# CPCIS_Connectors_P1_P6.net
KiCad netlist of a schematic drawn in Altium Designer
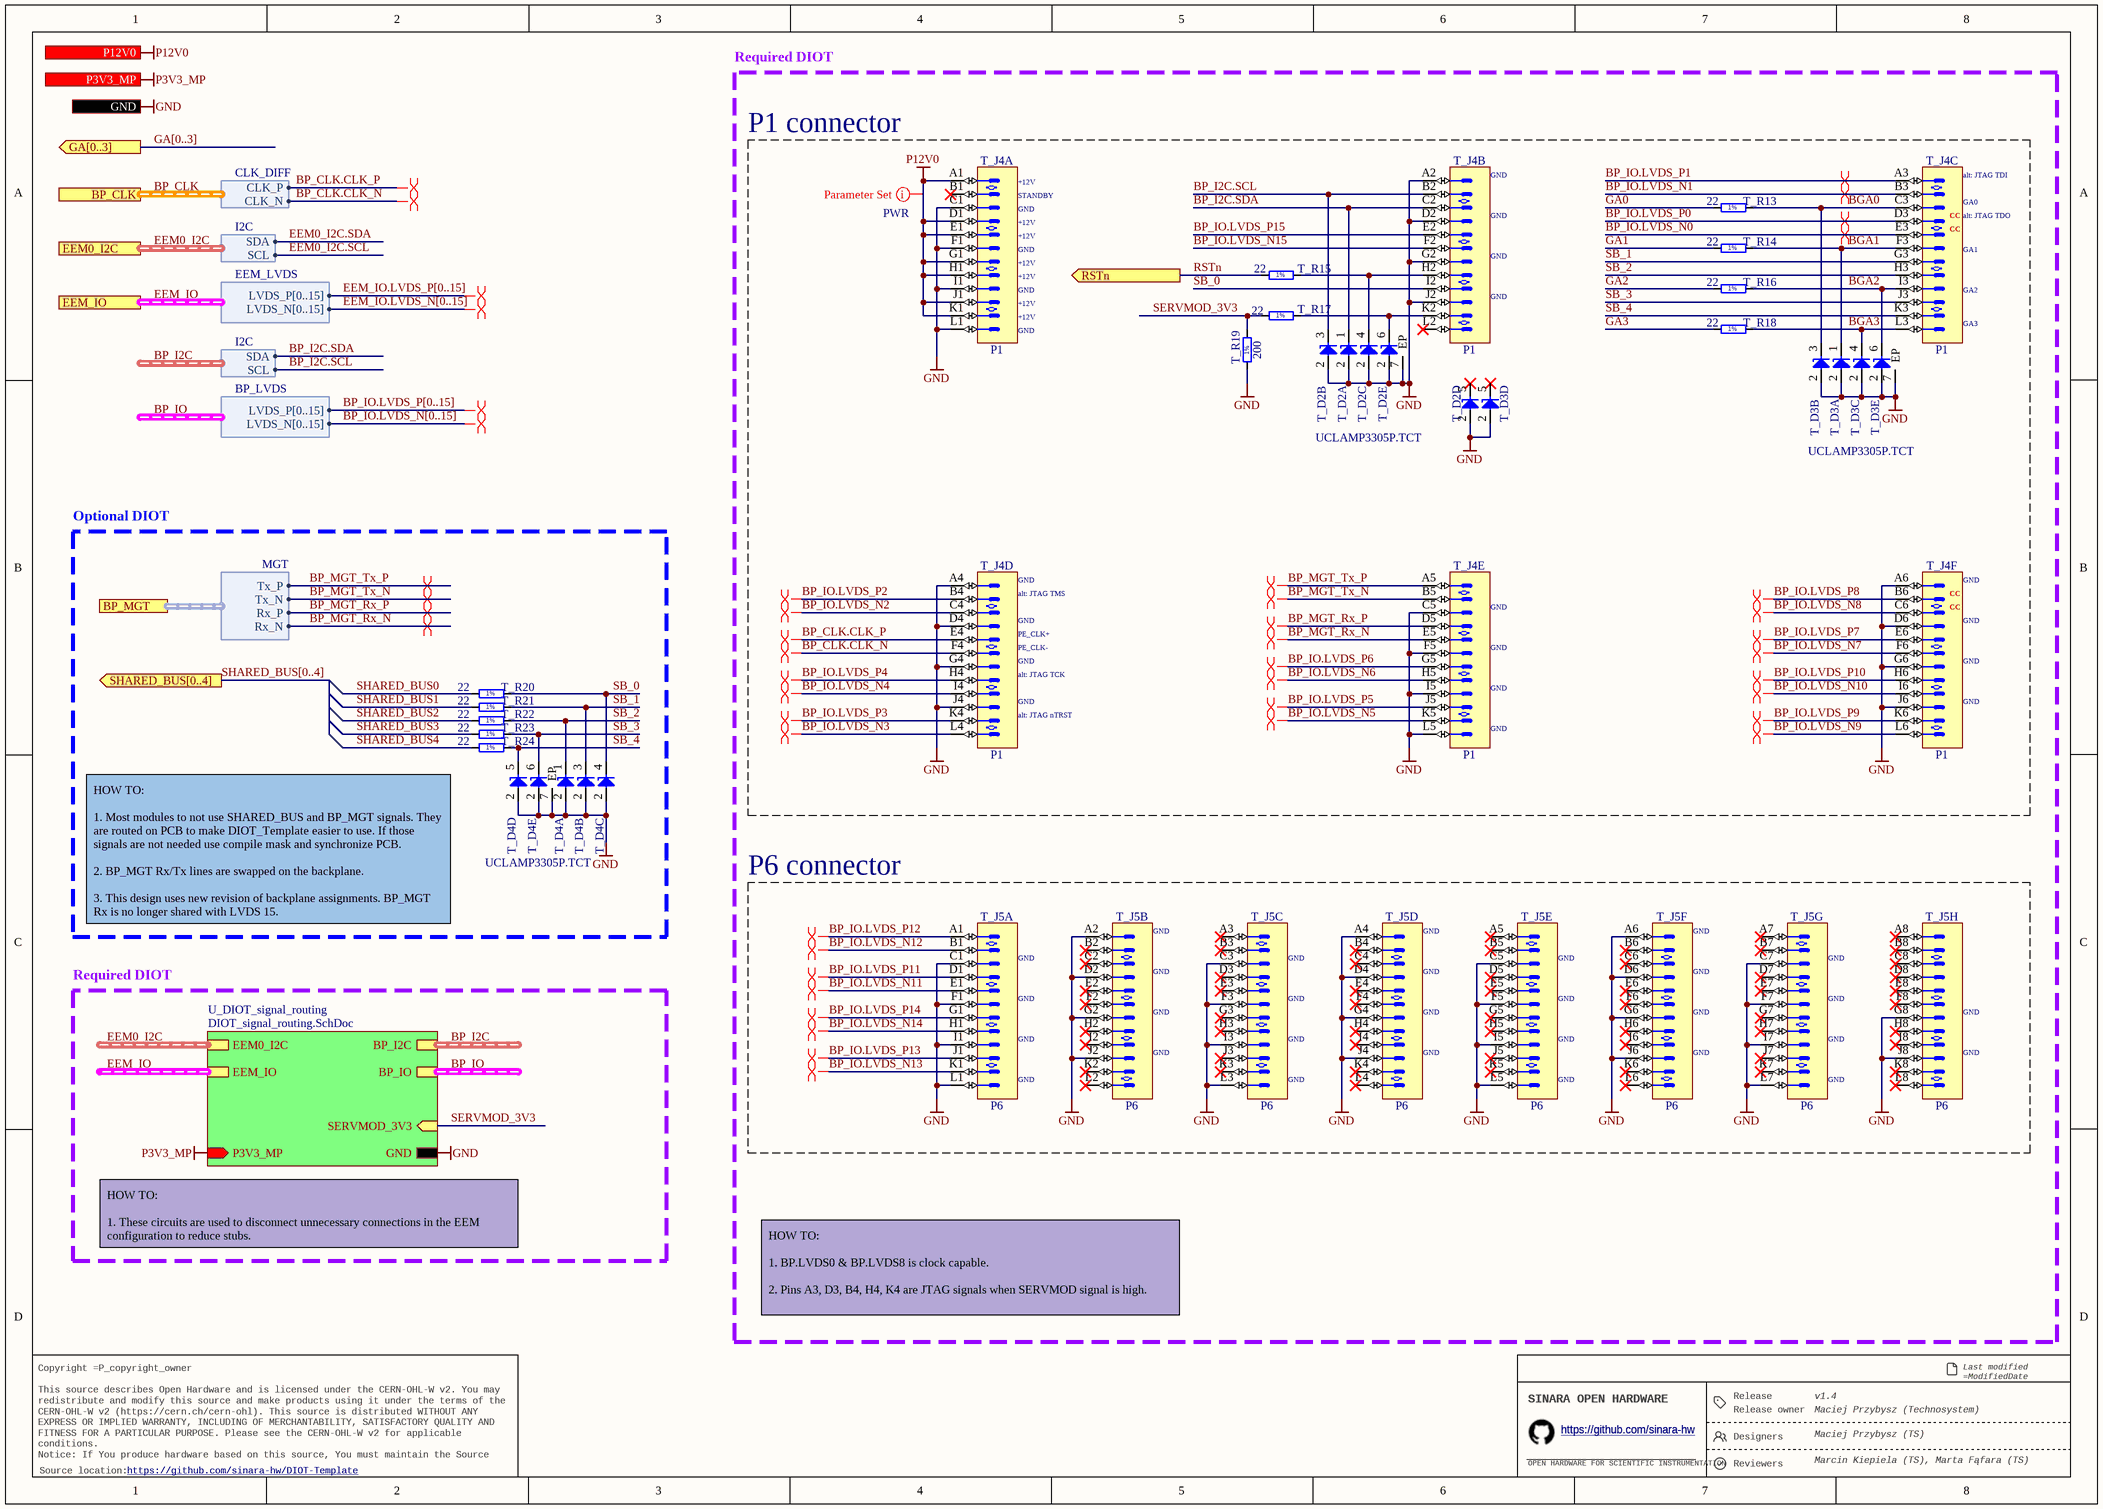
[diagram p0: CPCIS_Connectors_P1_P6.SchDoc]

(export (version "E")
  (design (tool "Eeschema 10.0.6"))
  (components
    (comp (ref "T_D2")
      (value "UCLAMP3305P.TCT")
      (footprint "SON50P160X65_HS-7N")
      (description "Diode TVS Quint Common Anode Uni-Dir 3.3V 40W 6-Pin SLP EP T/R")
      (libsource (lib "TechnoSystem Workspace") (part "D-AK-2"))
    )
    (comp (ref "T_D3")
      (value "UCLAMP3305P.TCT")
      (footprint "SON50P160X65_HS-7N")
      (description "Diode TVS Quint Common Anode Uni-Dir 3.3V 40W 6-Pin SLP EP T/R")
      (libsource (lib "TechnoSystem Workspace") (part "D-AK-2"))
    )
    (comp (ref "T_D4")
      (value "UCLAMP3305P.TCT")
      (footprint "SON50P160X65_HS-7N")
      (description "Diode TVS Quint Common Anode Uni-Dir 3.3V 40W 6-Pin SLP EP T/R")
      (libsource (lib "TechnoSystem Workspace") (part "D-AK-2"))
    )
    (comp (ref "T_J4")
      (value "P1")
      (footprint "AMPHENOL_10052825-101LF")
      (description "72 Contacts Header, 6 Columns, 4 Pairs per Column")
      (fields
        (field (name "PART NUMBER") "AMPHENOL_10052825-101LF")
        (field (name "MANUFACTURER") "AMPHENOL")
        (field (name "AUTHOR") "CERN DEM MR")
      )
      (libsource (lib "Connectors") (part "AMPHENOL_10052825-101LF"))
    )
    (comp (ref "T_J5")
      (value "P6")
      (footprint "AMPHENOL_10052838-101LF")
      (description "96 Contacts Header, 8 Columns, 4 Pairs per Column")
      (fields
        (field (name "PART NUMBER") "AMPHENOL_10052838-101LF")
        (field (name "MANUFACTURER") "AMPHENOL")
        (field (name "AUTHOR") "CERN DEM MR")
      )
      (libsource (lib "Connectors") (part "AMPHENOL_10052838-101LF"))
    )
    (comp (ref "T_R13")
      (value "22")
      (footprint "RESC1005X40N")
      (description "Resistor - 1%")
      (fields
        (field (name "PART NUMBER") "R0402_22R_1%_0.0625W_100PPM")
        (field (name "POWER") "0.0625W")
        (field (name "AUTHOR") "CERN DEM JLC")
      )
      (libsource (lib "Resistors") (part "Resistor - 1%"))
    )
    (comp (ref "T_R14")
      (value "22")
      (footprint "RESC1005X40N")
      (description "Resistor - 1%")
      (fields
        (field (name "PART NUMBER") "R0402_22R_1%_0.0625W_100PPM")
        (field (name "POWER") "0.0625W")
        (field (name "AUTHOR") "CERN DEM JLC")
      )
      (libsource (lib "Resistors") (part "Resistor - 1%"))
    )
    (comp (ref "T_R15")
      (value "22")
      (footprint "RESC1005X40N")
      (description "Resistor - 1%")
      (fields
        (field (name "PART NUMBER") "R0402_22R_1%_0.0625W_100PPM")
        (field (name "POWER") "0.0625W")
        (field (name "AUTHOR") "CERN DEM JLC")
      )
      (libsource (lib "Resistors") (part "Resistor - 1%"))
    )
    (comp (ref "T_R16")
      (value "22")
      (footprint "RESC1005X40N")
      (description "Resistor - 1%")
      (fields
        (field (name "PART NUMBER") "R0402_22R_1%_0.0625W_100PPM")
        (field (name "POWER") "0.0625W")
        (field (name "AUTHOR") "CERN DEM JLC")
      )
      (libsource (lib "Resistors") (part "Resistor - 1%"))
    )
    (comp (ref "T_R17")
      (value "22")
      (footprint "RESC1005X40N")
      (description "Resistor - 1%")
      (fields
        (field (name "PART NUMBER") "R0402_22R_1%_0.0625W_100PPM")
        (field (name "POWER") "0.0625W")
        (field (name "AUTHOR") "CERN DEM JLC")
      )
      (libsource (lib "Resistors") (part "Resistor - 1%"))
    )
    (comp (ref "T_R18")
      (value "22")
      (footprint "RESC1005X40N")
      (description "Resistor - 1%")
      (fields
        (field (name "PART NUMBER") "R0402_22R_1%_0.0625W_100PPM")
        (field (name "POWER") "0.0625W")
        (field (name "AUTHOR") "CERN DEM JLC")
      )
      (libsource (lib "Resistors") (part "Resistor - 1%"))
    )
    (comp (ref "T_R19")
      (value "200")
      (footprint "RESC1005X40N")
      (description "Resistor - 1%")
      (fields
        (field (name "PART NUMBER") "R0402_200R_1%_0.0625W_100PPM")
        (field (name "POWER") "0.0625W")
        (field (name "AUTHOR") "CERN DEM JLC")
      )
      (libsource (lib "Resistors") (part "Resistor - 1%"))
    )
    (comp (ref "T_R20")
      (value "22")
      (footprint "RESC1005X40N")
      (description "Resistor - 1%")
      (fields
        (field (name "PART NUMBER") "R0402_22R_1%_0.0625W_100PPM")
        (field (name "POWER") "0.0625W")
        (field (name "AUTHOR") "CERN DEM JLC")
      )
      (libsource (lib "Resistors") (part "Resistor - 1%"))
    )
    (comp (ref "T_R21")
      (value "22")
      (footprint "RESC1005X40N")
      (description "Resistor - 1%")
      (fields
        (field (name "PART NUMBER") "R0402_22R_1%_0.0625W_100PPM")
        (field (name "POWER") "0.0625W")
        (field (name "AUTHOR") "CERN DEM JLC")
      )
      (libsource (lib "Resistors") (part "Resistor - 1%"))
    )
    (comp (ref "T_R22")
      (value "22")
      (footprint "RESC1005X40N")
      (description "Resistor - 1%")
      (fields
        (field (name "PART NUMBER") "R0402_22R_1%_0.0625W_100PPM")
        (field (name "POWER") "0.0625W")
        (field (name "AUTHOR") "CERN DEM JLC")
      )
      (libsource (lib "Resistors") (part "Resistor - 1%"))
    )
    (comp (ref "T_R23")
      (value "22")
      (footprint "RESC1005X40N")
      (description "Resistor - 1%")
      (fields
        (field (name "PART NUMBER") "R0402_22R_1%_0.0625W_100PPM")
        (field (name "POWER") "0.0625W")
        (field (name "AUTHOR") "CERN DEM JLC")
      )
      (libsource (lib "Resistors") (part "Resistor - 1%"))
    )
    (comp (ref "T_R24")
      (value "22")
      (footprint "RESC1005X40N")
      (description "Resistor - 1%")
      (fields
        (field (name "PART NUMBER") "R0402_22R_1%_0.0625W_100PPM")
        (field (name "POWER") "0.0625W")
        (field (name "AUTHOR") "CERN DEM JLC")
      )
      (libsource (lib "Resistors") (part "Resistor - 1%"))
    )
  )
  (nets
    (net (code "43") (name "/BGA0") (class "Default")
      (node (ref "T_D3") (pin "3") (pinfunction "C_3") (pintype "passive"))
      (node (ref "T_J4") (pin "C3") (pinfunction "C3_C3") (pintype "bidirectional"))
      (node (ref "T_R13") (pin "2") (pinfunction "2_2") (pintype "passive"))
    )
    (net (code "44") (name "/BGA1") (class "Default")
      (node (ref "T_D3") (pin "1") (pinfunction "C_1") (pintype "passive"))
      (node (ref "T_J4") (pin "F3") (pinfunction "F3_F3") (pintype "bidirectional"))
      (node (ref "T_R14") (pin "2") (pinfunction "2_2") (pintype "passive"))
    )
    (net (code "45") (name "/BGA2") (class "Default")
      (node (ref "T_D3") (pin "6") (pinfunction "C_6") (pintype "passive"))
      (node (ref "T_J4") (pin "I3") (pinfunction "I3_I3") (pintype "bidirectional"))
      (node (ref "T_R16") (pin "2") (pinfunction "2_2") (pintype "passive"))
    )
    (net (code "46") (name "/BGA3") (class "Default")
      (node (ref "T_D3") (pin "4") (pinfunction "C_4") (pintype "passive"))
      (node (ref "T_J4") (pin "L3") (pinfunction "L3_L3") (pintype "bidirectional"))
      (node (ref "T_R18") (pin "2") (pinfunction "2_2") (pintype "passive"))
    )
    (net (code "47") (name "/BP_CLK.CLK_N") (class "Default")
      (node (ref "T_J4") (pin "F4") (pinfunction "F4_F4") (pintype "bidirectional"))
    )
    (net (code "48") (name "/BP_CLK.CLK_P") (class "Default")
      (node (ref "T_J4") (pin "E4") (pinfunction "E4_E4") (pintype "bidirectional"))
    )
    (net (code "50") (name "/BP_I2C.SCL") (class "Default")
      (node (ref "T_D2") (pin "3") (pinfunction "C_3") (pintype "passive"))
      (node (ref "T_J4") (pin "B2") (pinfunction "B2_B2") (pintype "bidirectional"))
    )
    (net (code "51") (name "/BP_I2C.SDA") (class "Default")
      (node (ref "T_D2") (pin "1") (pinfunction "C_1") (pintype "passive"))
      (node (ref "T_J4") (pin "C2") (pinfunction "C2_C2") (pintype "bidirectional"))
    )
    (net (code "53") (name "/BP_IO.LVDS_N0") (class "Default")
      (node (ref "T_J4") (pin "E3") (pinfunction "E3_E3") (pintype "bidirectional"))
    )
    (net (code "54") (name "/BP_IO.LVDS_N1") (class "Default")
      (node (ref "T_J4") (pin "B3") (pinfunction "B3_B3") (pintype "bidirectional"))
    )
    (net (code "55") (name "/BP_IO.LVDS_N2") (class "Default")
      (node (ref "T_J4") (pin "C4") (pinfunction "C4_C4") (pintype "bidirectional"))
    )
    (net (code "56") (name "/BP_IO.LVDS_N3") (class "Default")
      (node (ref "T_J4") (pin "L4") (pinfunction "L4_L4") (pintype "bidirectional"))
    )
    (net (code "57") (name "/BP_IO.LVDS_N4") (class "Default")
      (node (ref "T_J4") (pin "I4") (pinfunction "I4_I4") (pintype "bidirectional"))
    )
    (net (code "58") (name "/BP_IO.LVDS_N5") (class "Default")
      (node (ref "T_J4") (pin "K5") (pinfunction "K5_K5") (pintype "bidirectional"))
    )
    (net (code "59") (name "/BP_IO.LVDS_N6") (class "Default")
      (node (ref "T_J4") (pin "H5") (pinfunction "H5_H5") (pintype "bidirectional"))
    )
    (net (code "60") (name "/BP_IO.LVDS_N7") (class "Default")
      (node (ref "T_J4") (pin "F6") (pinfunction "F6_F6") (pintype "bidirectional"))
    )
    (net (code "61") (name "/BP_IO.LVDS_N8") (class "Default")
      (node (ref "T_J4") (pin "C6") (pinfunction "C6_C6") (pintype "bidirectional"))
    )
    (net (code "62") (name "/BP_IO.LVDS_N9") (class "Default")
      (node (ref "T_J4") (pin "L6") (pinfunction "L6_L6") (pintype "bidirectional"))
    )
    (net (code "63") (name "/BP_IO.LVDS_N10") (class "Default")
      (node (ref "T_J4") (pin "I6") (pinfunction "I6_I6") (pintype "bidirectional"))
    )
    (net (code "64") (name "/BP_IO.LVDS_N11") (class "Default")
      (node (ref "T_J5") (pin "E1") (pinfunction "E1_E1") (pintype "bidirectional"))
    )
    (net (code "65") (name "/BP_IO.LVDS_N12") (class "Default")
      (node (ref "T_J5") (pin "B1") (pinfunction "B1_B1") (pintype "bidirectional"))
    )
    (net (code "66") (name "/BP_IO.LVDS_N13") (class "Default")
      (node (ref "T_J5") (pin "K1") (pinfunction "K1_K1") (pintype "bidirectional"))
    )
    (net (code "67") (name "/BP_IO.LVDS_N14") (class "Default")
      (node (ref "T_J5") (pin "H1") (pinfunction "H1_H1") (pintype "bidirectional"))
    )
    (net (code "68") (name "/BP_IO.LVDS_N15") (class "Default")
      (node (ref "T_J4") (pin "F2") (pinfunction "F2_F2") (pintype "bidirectional"))
    )
    (net (code "70") (name "/BP_IO.LVDS_P0") (class "Default")
      (node (ref "T_J4") (pin "D3") (pinfunction "D3_D3") (pintype "bidirectional"))
    )
    (net (code "71") (name "/BP_IO.LVDS_P1") (class "Default")
      (node (ref "T_J4") (pin "A3") (pinfunction "A3_A3") (pintype "bidirectional"))
    )
    (net (code "72") (name "/BP_IO.LVDS_P2") (class "Default")
      (node (ref "T_J4") (pin "B4") (pinfunction "B4_B4") (pintype "bidirectional"))
    )
    (net (code "73") (name "/BP_IO.LVDS_P3") (class "Default")
      (node (ref "T_J4") (pin "K4") (pinfunction "K4_K4") (pintype "bidirectional"))
    )
    (net (code "74") (name "/BP_IO.LVDS_P4") (class "Default")
      (node (ref "T_J4") (pin "H4") (pinfunction "H4_H4") (pintype "bidirectional"))
    )
    (net (code "75") (name "/BP_IO.LVDS_P5") (class "Default")
      (node (ref "T_J4") (pin "J5") (pinfunction "J5_J5") (pintype "bidirectional"))
    )
    (net (code "76") (name "/BP_IO.LVDS_P6") (class "Default")
      (node (ref "T_J4") (pin "G5") (pinfunction "G5_G5") (pintype "bidirectional"))
    )
    (net (code "77") (name "/BP_IO.LVDS_P7") (class "Default")
      (node (ref "T_J4") (pin "E6") (pinfunction "E6_E6") (pintype "bidirectional"))
    )
    (net (code "78") (name "/BP_IO.LVDS_P8") (class "Default")
      (node (ref "T_J4") (pin "B6") (pinfunction "B6_B6") (pintype "bidirectional"))
    )
    (net (code "79") (name "/BP_IO.LVDS_P9") (class "Default")
      (node (ref "T_J4") (pin "K6") (pinfunction "K6_K6") (pintype "bidirectional"))
    )
    (net (code "80") (name "/BP_IO.LVDS_P10") (class "Default")
      (node (ref "T_J4") (pin "H6") (pinfunction "H6_H6") (pintype "bidirectional"))
    )
    (net (code "81") (name "/BP_IO.LVDS_P11") (class "Default")
      (node (ref "T_J5") (pin "D1") (pinfunction "D1_D1") (pintype "bidirectional"))
    )
    (net (code "82") (name "/BP_IO.LVDS_P12") (class "Default")
      (node (ref "T_J5") (pin "A1") (pinfunction "A1_A1") (pintype "bidirectional"))
    )
    (net (code "83") (name "/BP_IO.LVDS_P13") (class "Default")
      (node (ref "T_J5") (pin "J1") (pinfunction "J1_J1") (pintype "bidirectional"))
    )
    (net (code "84") (name "/BP_IO.LVDS_P14") (class "Default")
      (node (ref "T_J5") (pin "G1") (pinfunction "G1_G1") (pintype "bidirectional"))
    )
    (net (code "85") (name "/BP_IO.LVDS_P15") (class "Default")
      (node (ref "T_J4") (pin "E2") (pinfunction "E2_E2") (pintype "bidirectional"))
    )
    (net (code "88") (name "/BP_MGT_Rx_N") (class "Default")
      (node (ref "T_J4") (pin "E5") (pinfunction "E5_E5") (pintype "bidirectional"))
    )
    (net (code "89") (name "/BP_MGT_Rx_P") (class "Default")
      (node (ref "T_J4") (pin "D5") (pinfunction "D5_D5") (pintype "bidirectional"))
    )
    (net (code "90") (name "/BP_MGT_Tx_N") (class "Default")
      (node (ref "T_J4") (pin "B5") (pinfunction "B5_B5") (pintype "bidirectional"))
    )
    (net (code "91") (name "/BP_MGT_Tx_P") (class "Default")
      (node (ref "T_J4") (pin "A5") (pinfunction "A5_A5") (pintype "bidirectional"))
    )
    (net (code "98") (name "/GA0") (class "Default")
      (node (ref "T_R13") (pin "1") (pinfunction "1_1") (pintype "passive"))
    )
    (net (code "99") (name "/GA1") (class "Default")
      (node (ref "T_R14") (pin "1") (pinfunction "1_1") (pintype "passive"))
    )
    (net (code "100") (name "/GA2") (class "Default")
      (node (ref "T_R16") (pin "1") (pinfunction "1_1") (pintype "passive"))
    )
    (net (code "101") (name "/GA3") (class "Default")
      (node (ref "T_R18") (pin "1") (pinfunction "1_1") (pintype "passive"))
    )
    (net (code "103") (name "/RSTn") (class "Default")
      (node (ref "T_R15") (pin "1") (pinfunction "1_1") (pintype "passive"))
    )
    (net (code "104") (name "/SB_0") (class "Default")
      (node (ref "T_D4") (pin "4") (pinfunction "C_4") (pintype "passive"))
      (node (ref "T_J4") (pin "I2") (pinfunction "I2_I2") (pintype "bidirectional"))
      (node (ref "T_R20") (pin "2") (pinfunction "2_2") (pintype "passive"))
    )
    (net (code "105") (name "/SB_1") (class "Default")
      (node (ref "T_D4") (pin "3") (pinfunction "C_3") (pintype "passive"))
      (node (ref "T_J4") (pin "G3") (pinfunction "G3_G3") (pintype "bidirectional"))
      (node (ref "T_R21") (pin "2") (pinfunction "2_2") (pintype "passive"))
    )
    (net (code "106") (name "/SB_2") (class "Default")
      (node (ref "T_D4") (pin "1") (pinfunction "C_1") (pintype "passive"))
      (node (ref "T_J4") (pin "H3") (pinfunction "H3_H3") (pintype "bidirectional"))
      (node (ref "T_R22") (pin "2") (pinfunction "2_2") (pintype "passive"))
    )
    (net (code "107") (name "/SB_3") (class "Default")
      (node (ref "T_D4") (pin "6") (pinfunction "C_6") (pintype "passive"))
      (node (ref "T_J4") (pin "J3") (pinfunction "J3_J3") (pintype "bidirectional"))
      (node (ref "T_R23") (pin "2") (pinfunction "2_2") (pintype "passive"))
    )
    (net (code "108") (name "/SB_4") (class "Default")
      (node (ref "T_D4") (pin "5") (pinfunction "C_5") (pintype "passive"))
      (node (ref "T_J4") (pin "K3") (pinfunction "K3_K3") (pintype "bidirectional"))
      (node (ref "T_R24") (pin "2") (pinfunction "2_2") (pintype "passive"))
    )
    (net (code "109") (name "/SERVMOD_3V3") (class "Default")
      (node (ref "T_R17") (pin "1") (pinfunction "1_1") (pintype "passive"))
      (node (ref "T_R19") (pin "2") (pinfunction "2_2") (pintype "passive"))
    )
    (net (code "110") (name "/SHARED_BUS0") (class "Default")
      (node (ref "T_R20") (pin "1") (pinfunction "1_1") (pintype "passive"))
    )
    (net (code "111") (name "/SHARED_BUS1") (class "Default")
      (node (ref "T_R21") (pin "1") (pinfunction "1_1") (pintype "passive"))
    )
    (net (code "112") (name "/SHARED_BUS2") (class "Default")
      (node (ref "T_R22") (pin "1") (pinfunction "1_1") (pintype "passive"))
    )
    (net (code "113") (name "/SHARED_BUS3") (class "Default")
      (node (ref "T_R23") (pin "1") (pinfunction "1_1") (pintype "passive"))
    )
    (net (code "114") (name "/SHARED_BUS4") (class "Default")
      (node (ref "T_R24") (pin "1") (pinfunction "1_1") (pintype "passive"))
    )
    (net (code "121") (name "GND") (class "Default")
      (node (ref "T_D2") (pin "2") (pinfunction "A_2") (pintype "passive"))
      (node (ref "T_D2") (pin "7") (pinfunction "EP_7") (pintype "passive"))
      (node (ref "T_D3") (pin "2") (pinfunction "A_2") (pintype "passive"))
      (node (ref "T_D3") (pin "7") (pinfunction "EP_7") (pintype "passive"))
      (node (ref "T_D4") (pin "2") (pinfunction "A_2") (pintype "passive"))
      (node (ref "T_D4") (pin "7") (pinfunction "EP_7") (pintype "passive"))
      (node (ref "T_J4") (pin "A2") (pinfunction "A2_A2") (pintype "bidirectional"))
      (node (ref "T_J4") (pin "A4") (pinfunction "A4_A4") (pintype "bidirectional"))
      (node (ref "T_J4") (pin "A6") (pinfunction "A6_A6") (pintype "bidirectional"))
      (node (ref "T_J4") (pin "C1") (pinfunction "C1_C1") (pintype "bidirectional"))
      (node (ref "T_J4") (pin "C5") (pinfunction "C5_C5") (pintype "bidirectional"))
      (node (ref "T_J4") (pin "D2") (pinfunction "D2_D2") (pintype "bidirectional"))
      (node (ref "T_J4") (pin "D4") (pinfunction "D4_D4") (pintype "bidirectional"))
      (node (ref "T_J4") (pin "D6") (pinfunction "D6_D6") (pintype "bidirectional"))
      (node (ref "T_J4") (pin "F1") (pinfunction "F1_F1") (pintype "bidirectional"))
      (node (ref "T_J4") (pin "F5") (pinfunction "F5_F5") (pintype "bidirectional"))
      (node (ref "T_J4") (pin "G2") (pinfunction "G2_G2") (pintype "bidirectional"))
      (node (ref "T_J4") (pin "G4") (pinfunction "G4_G4") (pintype "bidirectional"))
      (node (ref "T_J4") (pin "G6") (pinfunction "G6_G6") (pintype "bidirectional"))
      (node (ref "T_J4") (pin "I1") (pinfunction "I1_I1") (pintype "bidirectional"))
      (node (ref "T_J4") (pin "I5") (pinfunction "I5_I5") (pintype "bidirectional"))
      (node (ref "T_J4") (pin "J2") (pinfunction "J2_J2") (pintype "bidirectional"))
      (node (ref "T_J4") (pin "J4") (pinfunction "J4_J4") (pintype "bidirectional"))
      (node (ref "T_J4") (pin "J6") (pinfunction "J6_J6") (pintype "bidirectional"))
      (node (ref "T_J4") (pin "L1") (pinfunction "L1_L1") (pintype "bidirectional"))
      (node (ref "T_J4") (pin "L5") (pinfunction "L5_L5") (pintype "bidirectional"))
      (node (ref "T_J5") (pin "A2") (pinfunction "A2_A2") (pintype "bidirectional"))
      (node (ref "T_J5") (pin "A4") (pinfunction "A4_A4") (pintype "bidirectional"))
      (node (ref "T_J5") (pin "A6") (pinfunction "A6_A6") (pintype "bidirectional"))
      (node (ref "T_J5") (pin "C1") (pinfunction "C1_C1") (pintype "bidirectional"))
      (node (ref "T_J5") (pin "C3") (pinfunction "C3_C3") (pintype "bidirectional"))
      (node (ref "T_J5") (pin "C5") (pinfunction "C5_C5") (pintype "bidirectional"))
      (node (ref "T_J5") (pin "C7") (pinfunction "C7_C7") (pintype "bidirectional"))
      (node (ref "T_J5") (pin "D2") (pinfunction "D2_D2") (pintype "bidirectional"))
      (node (ref "T_J5") (pin "D4") (pinfunction "D4_D4") (pintype "bidirectional"))
      (node (ref "T_J5") (pin "D6") (pinfunction "D6_D6") (pintype "bidirectional"))
      (node (ref "T_J5") (pin "F1") (pinfunction "F1_F1") (pintype "bidirectional"))
      (node (ref "T_J5") (pin "F3") (pinfunction "F3_F3") (pintype "bidirectional"))
      (node (ref "T_J5") (pin "F5") (pinfunction "F5_F5") (pintype "bidirectional"))
      (node (ref "T_J5") (pin "F7") (pinfunction "F7_F7") (pintype "bidirectional"))
      (node (ref "T_J5") (pin "G2") (pinfunction "G2_G2") (pintype "bidirectional"))
      (node (ref "T_J5") (pin "G4") (pinfunction "G4_G4") (pintype "bidirectional"))
      (node (ref "T_J5") (pin "G6") (pinfunction "G6_G6") (pintype "bidirectional"))
      (node (ref "T_J5") (pin "G8") (pinfunction "G8_G8") (pintype "bidirectional"))
      (node (ref "T_J5") (pin "I1") (pinfunction "I1_I1") (pintype "bidirectional"))
      (node (ref "T_J5") (pin "I3") (pinfunction "I3_I3") (pintype "bidirectional"))
      (node (ref "T_J5") (pin "I5") (pinfunction "I5_I5") (pintype "bidirectional"))
      (node (ref "T_J5") (pin "I7") (pinfunction "I7_I7") (pintype "bidirectional"))
      (node (ref "T_J5") (pin "J2") (pinfunction "J2_J2") (pintype "bidirectional"))
      (node (ref "T_J5") (pin "J4") (pinfunction "J4_J4") (pintype "bidirectional"))
      (node (ref "T_J5") (pin "J6") (pinfunction "J6_J6") (pintype "bidirectional"))
      (node (ref "T_J5") (pin "J8") (pinfunction "J8_J8") (pintype "bidirectional"))
      (node (ref "T_J5") (pin "L1") (pinfunction "L1_L1") (pintype "bidirectional"))
      (node (ref "T_J5") (pin "L3") (pinfunction "L3_L3") (pintype "bidirectional"))
      (node (ref "T_J5") (pin "L5") (pinfunction "L5_L5") (pintype "bidirectional"))
      (node (ref "T_J5") (pin "L7") (pinfunction "L7_L7") (pintype "bidirectional"))
      (node (ref "T_R19") (pin "1") (pinfunction "1_1") (pintype "passive"))
    )
    (net (code "122") (name "Net-(T_D2C-C)") (class "Default")
      (node (ref "T_D2") (pin "4") (pinfunction "C_4") (pintype "passive"))
      (node (ref "T_J4") (pin "H2") (pinfunction "H2_H2") (pintype "bidirectional"))
      (node (ref "T_R15") (pin "2") (pinfunction "2_2") (pintype "passive"))
    )
    (net (code "123") (name "Net-(T_D2E-C)") (class "Default")
      (node (ref "T_D2") (pin "6") (pinfunction "C_6") (pintype "passive"))
      (node (ref "T_J4") (pin "K2") (pinfunction "K2_K2") (pintype "bidirectional"))
      (node (ref "T_R17") (pin "2") (pinfunction "2_2") (pintype "passive"))
    )
    (net (code "125") (name "P12V0") (class "Default")
      (node (ref "T_J4") (pin "A1") (pinfunction "A1_A1") (pintype "bidirectional"))
      (node (ref "T_J4") (pin "D1") (pinfunction "D1_D1") (pintype "bidirectional"))
      (node (ref "T_J4") (pin "E1") (pinfunction "E1_E1") (pintype "bidirectional"))
      (node (ref "T_J4") (pin "G1") (pinfunction "G1_G1") (pintype "bidirectional"))
      (node (ref "T_J4") (pin "H1") (pinfunction "H1_H1") (pintype "bidirectional"))
      (node (ref "T_J4") (pin "J1") (pinfunction "J1_J1") (pintype "bidirectional"))
      (node (ref "T_J4") (pin "K1") (pinfunction "K1_K1") (pintype "bidirectional"))
    )
    (net (code "126") (name "unconnected-(T_D2D-C-Pad5)") (class "Default")
      (node (ref "T_D2") (pin "5") (pinfunction "C_5") (pintype "passive+no_connect"))
    )
    (net (code "127") (name "unconnected-(T_D3D-C-Pad5)") (class "Default")
      (node (ref "T_D3") (pin "5") (pinfunction "C_5") (pintype "passive+no_connect"))
    )
    (net (code "128") (name "unconnected-(T_J4-PadB1)") (class "Default")
      (node (ref "T_J4") (pin "B1") (pinfunction "B1_B1") (pintype "bidirectional+no_connect"))
    )
    (net (code "129") (name "unconnected-(T_J4-PadL2)") (class "Default")
      (node (ref "T_J4") (pin "L2") (pinfunction "L2_L2") (pintype "bidirectional+no_connect"))
    )
    (net (code "130") (name "unconnected-(T_J5-PadA3)") (class "Default")
      (node (ref "T_J5") (pin "A3") (pinfunction "A3_A3") (pintype "bidirectional+no_connect"))
    )
    (net (code "131") (name "unconnected-(T_J5-PadA5)") (class "Default")
      (node (ref "T_J5") (pin "A5") (pinfunction "A5_A5") (pintype "bidirectional+no_connect"))
    )
    (net (code "132") (name "unconnected-(T_J5-PadA7)") (class "Default")
      (node (ref "T_J5") (pin "A7") (pinfunction "A7_A7") (pintype "bidirectional+no_connect"))
    )
    (net (code "133") (name "unconnected-(T_J5-PadA8)") (class "Default")
      (node (ref "T_J5") (pin "A8") (pinfunction "A8_A8") (pintype "bidirectional+no_connect"))
    )
    (net (code "134") (name "unconnected-(T_J5-PadB2)") (class "Default")
      (node (ref "T_J5") (pin "B2") (pinfunction "B2_B2") (pintype "bidirectional+no_connect"))
    )
    (net (code "135") (name "unconnected-(T_J5-PadB3)") (class "Default")
      (node (ref "T_J5") (pin "B3") (pinfunction "B3_B3") (pintype "bidirectional+no_connect"))
    )
    (net (code "136") (name "unconnected-(T_J5-PadB4)") (class "Default")
      (node (ref "T_J5") (pin "B4") (pinfunction "B4_B4") (pintype "bidirectional+no_connect"))
    )
    (net (code "137") (name "unconnected-(T_J5-PadB5)") (class "Default")
      (node (ref "T_J5") (pin "B5") (pinfunction "B5_B5") (pintype "bidirectional+no_connect"))
    )
    (net (code "138") (name "unconnected-(T_J5-PadB6)") (class "Default")
      (node (ref "T_J5") (pin "B6") (pinfunction "B6_B6") (pintype "bidirectional+no_connect"))
    )
    (net (code "139") (name "unconnected-(T_J5-PadB7)") (class "Default")
      (node (ref "T_J5") (pin "B7") (pinfunction "B7_B7") (pintype "bidirectional+no_connect"))
    )
    (net (code "140") (name "unconnected-(T_J5-PadB8)") (class "Default")
      (node (ref "T_J5") (pin "B8") (pinfunction "B8_B8") (pintype "bidirectional+no_connect"))
    )
    (net (code "141") (name "unconnected-(T_J5-PadC2)") (class "Default")
      (node (ref "T_J5") (pin "C2") (pinfunction "C2_C2") (pintype "bidirectional+no_connect"))
    )
    (net (code "142") (name "unconnected-(T_J5-PadC4)") (class "Default")
      (node (ref "T_J5") (pin "C4") (pinfunction "C4_C4") (pintype "bidirectional+no_connect"))
    )
    (net (code "143") (name "unconnected-(T_J5-PadC6)") (class "Default")
      (node (ref "T_J5") (pin "C6") (pinfunction "C6_C6") (pintype "bidirectional+no_connect"))
    )
    (net (code "144") (name "unconnected-(T_J5-PadC8)") (class "Default")
      (node (ref "T_J5") (pin "C8") (pinfunction "C8_C8") (pintype "bidirectional+no_connect"))
    )
    (net (code "145") (name "unconnected-(T_J5-PadD3)") (class "Default")
      (node (ref "T_J5") (pin "D3") (pinfunction "D3_D3") (pintype "bidirectional+no_connect"))
    )
    (net (code "146") (name "unconnected-(T_J5-PadD5)") (class "Default")
      (node (ref "T_J5") (pin "D5") (pinfunction "D5_D5") (pintype "bidirectional+no_connect"))
    )
    (net (code "147") (name "unconnected-(T_J5-PadD7)") (class "Default")
      (node (ref "T_J5") (pin "D7") (pinfunction "D7_D7") (pintype "bidirectional+no_connect"))
    )
    (net (code "148") (name "unconnected-(T_J5-PadD8)") (class "Default")
      (node (ref "T_J5") (pin "D8") (pinfunction "D8_D8") (pintype "bidirectional+no_connect"))
    )
    (net (code "149") (name "unconnected-(T_J5-PadE2)") (class "Default")
      (node (ref "T_J5") (pin "E2") (pinfunction "E2_E2") (pintype "bidirectional+no_connect"))
    )
    (net (code "150") (name "unconnected-(T_J5-PadE3)") (class "Default")
      (node (ref "T_J5") (pin "E3") (pinfunction "E3_E3") (pintype "bidirectional+no_connect"))
    )
    (net (code "151") (name "unconnected-(T_J5-PadE4)") (class "Default")
      (node (ref "T_J5") (pin "E4") (pinfunction "E4_E4") (pintype "bidirectional+no_connect"))
    )
    (net (code "152") (name "unconnected-(T_J5-PadE5)") (class "Default")
      (node (ref "T_J5") (pin "E5") (pinfunction "E5_E5") (pintype "bidirectional+no_connect"))
    )
    (net (code "153") (name "unconnected-(T_J5-PadE6)") (class "Default")
      (node (ref "T_J5") (pin "E6") (pinfunction "E6_E6") (pintype "bidirectional+no_connect"))
    )
    (net (code "154") (name "unconnected-(T_J5-PadE7)") (class "Default")
      (node (ref "T_J5") (pin "E7") (pinfunction "E7_E7") (pintype "bidirectional+no_connect"))
    )
    (net (code "155") (name "unconnected-(T_J5-PadE8)") (class "Default")
      (node (ref "T_J5") (pin "E8") (pinfunction "E8_E8") (pintype "bidirectional+no_connect"))
    )
    (net (code "156") (name "unconnected-(T_J5-PadF2)") (class "Default")
      (node (ref "T_J5") (pin "F2") (pinfunction "F2_F2") (pintype "bidirectional+no_connect"))
    )
    (net (code "157") (name "unconnected-(T_J5-PadF4)") (class "Default")
      (node (ref "T_J5") (pin "F4") (pinfunction "F4_F4") (pintype "bidirectional+no_connect"))
    )
    (net (code "158") (name "unconnected-(T_J5-PadF6)") (class "Default")
      (node (ref "T_J5") (pin "F6") (pinfunction "F6_F6") (pintype "bidirectional+no_connect"))
    )
    (net (code "159") (name "unconnected-(T_J5-PadF8)") (class "Default")
      (node (ref "T_J5") (pin "F8") (pinfunction "F8_F8") (pintype "bidirectional+no_connect"))
    )
    (net (code "160") (name "unconnected-(T_J5-PadG3)") (class "Default")
      (node (ref "T_J5") (pin "G3") (pinfunction "G3_G3") (pintype "bidirectional+no_connect"))
    )
    (net (code "161") (name "unconnected-(T_J5-PadG5)") (class "Default")
      (node (ref "T_J5") (pin "G5") (pinfunction "G5_G5") (pintype "bidirectional+no_connect"))
    )
    (net (code "162") (name "unconnected-(T_J5-PadG7)") (class "Default")
      (node (ref "T_J5") (pin "G7") (pinfunction "G7_G7") (pintype "bidirectional+no_connect"))
    )
    (net (code "163") (name "unconnected-(T_J5-PadH2)") (class "Default")
      (node (ref "T_J5") (pin "H2") (pinfunction "H2_H2") (pintype "bidirectional+no_connect"))
    )
    (net (code "164") (name "unconnected-(T_J5-PadH3)") (class "Default")
      (node (ref "T_J5") (pin "H3") (pinfunction "H3_H3") (pintype "bidirectional+no_connect"))
    )
    (net (code "165") (name "unconnected-(T_J5-PadH4)") (class "Default")
      (node (ref "T_J5") (pin "H4") (pinfunction "H4_H4") (pintype "bidirectional+no_connect"))
    )
    (net (code "166") (name "unconnected-(T_J5-PadH5)") (class "Default")
      (node (ref "T_J5") (pin "H5") (pinfunction "H5_H5") (pintype "bidirectional+no_connect"))
    )
    (net (code "167") (name "unconnected-(T_J5-PadH6)") (class "Default")
      (node (ref "T_J5") (pin "H6") (pinfunction "H6_H6") (pintype "bidirectional+no_connect"))
    )
    (net (code "168") (name "unconnected-(T_J5-PadH7)") (class "Default")
      (node (ref "T_J5") (pin "H7") (pinfunction "H7_H7") (pintype "bidirectional+no_connect"))
    )
    (net (code "169") (name "unconnected-(T_J5-PadH8)") (class "Default")
      (node (ref "T_J5") (pin "H8") (pinfunction "H8_H8") (pintype "bidirectional+no_connect"))
    )
    (net (code "170") (name "unconnected-(T_J5-PadI2)") (class "Default")
      (node (ref "T_J5") (pin "I2") (pinfunction "I2_I2") (pintype "bidirectional+no_connect"))
    )
    (net (code "171") (name "unconnected-(T_J5-PadI4)") (class "Default")
      (node (ref "T_J5") (pin "I4") (pinfunction "I4_I4") (pintype "bidirectional+no_connect"))
    )
    (net (code "172") (name "unconnected-(T_J5-PadI6)") (class "Default")
      (node (ref "T_J5") (pin "I6") (pinfunction "I6_I6") (pintype "bidirectional+no_connect"))
    )
    (net (code "173") (name "unconnected-(T_J5-PadI8)") (class "Default")
      (node (ref "T_J5") (pin "I8") (pinfunction "I8_I8") (pintype "bidirectional+no_connect"))
    )
    (net (code "174") (name "unconnected-(T_J5-PadJ3)") (class "Default")
      (node (ref "T_J5") (pin "J3") (pinfunction "J3_J3") (pintype "bidirectional+no_connect"))
    )
    (net (code "175") (name "unconnected-(T_J5-PadJ5)") (class "Default")
      (node (ref "T_J5") (pin "J5") (pinfunction "J5_J5") (pintype "bidirectional+no_connect"))
    )
    (net (code "176") (name "unconnected-(T_J5-PadJ7)") (class "Default")
      (node (ref "T_J5") (pin "J7") (pinfunction "J7_J7") (pintype "bidirectional+no_connect"))
    )
    (net (code "177") (name "unconnected-(T_J5-PadK2)") (class "Default")
      (node (ref "T_J5") (pin "K2") (pinfunction "K2_K2") (pintype "bidirectional+no_connect"))
    )
    (net (code "178") (name "unconnected-(T_J5-PadK3)") (class "Default")
      (node (ref "T_J5") (pin "K3") (pinfunction "K3_K3") (pintype "bidirectional+no_connect"))
    )
    (net (code "179") (name "unconnected-(T_J5-PadK4)") (class "Default")
      (node (ref "T_J5") (pin "K4") (pinfunction "K4_K4") (pintype "bidirectional+no_connect"))
    )
    (net (code "180") (name "unconnected-(T_J5-PadK5)") (class "Default")
      (node (ref "T_J5") (pin "K5") (pinfunction "K5_K5") (pintype "bidirectional+no_connect"))
    )
    (net (code "181") (name "unconnected-(T_J5-PadK6)") (class "Default")
      (node (ref "T_J5") (pin "K6") (pinfunction "K6_K6") (pintype "bidirectional+no_connect"))
    )
    (net (code "182") (name "unconnected-(T_J5-PadK7)") (class "Default")
      (node (ref "T_J5") (pin "K7") (pinfunction "K7_K7") (pintype "bidirectional+no_connect"))
    )
    (net (code "183") (name "unconnected-(T_J5-PadK8)") (class "Default")
      (node (ref "T_J5") (pin "K8") (pinfunction "K8_K8") (pintype "bidirectional+no_connect"))
    )
    (net (code "184") (name "unconnected-(T_J5-PadL2)") (class "Default")
      (node (ref "T_J5") (pin "L2") (pinfunction "L2_L2") (pintype "bidirectional+no_connect"))
    )
    (net (code "185") (name "unconnected-(T_J5-PadL4)") (class "Default")
      (node (ref "T_J5") (pin "L4") (pinfunction "L4_L4") (pintype "bidirectional+no_connect"))
    )
    (net (code "186") (name "unconnected-(T_J5-PadL6)") (class "Default")
      (node (ref "T_J5") (pin "L6") (pinfunction "L6_L6") (pintype "bidirectional+no_connect"))
    )
    (net (code "187") (name "unconnected-(T_J5-PadL8)") (class "Default")
      (node (ref "T_J5") (pin "L8") (pinfunction "L8_L8") (pintype "bidirectional+no_connect"))
    )
  )
)
